# Sensing.net
KiCad netlist of a schematic drawn in Altium Designer
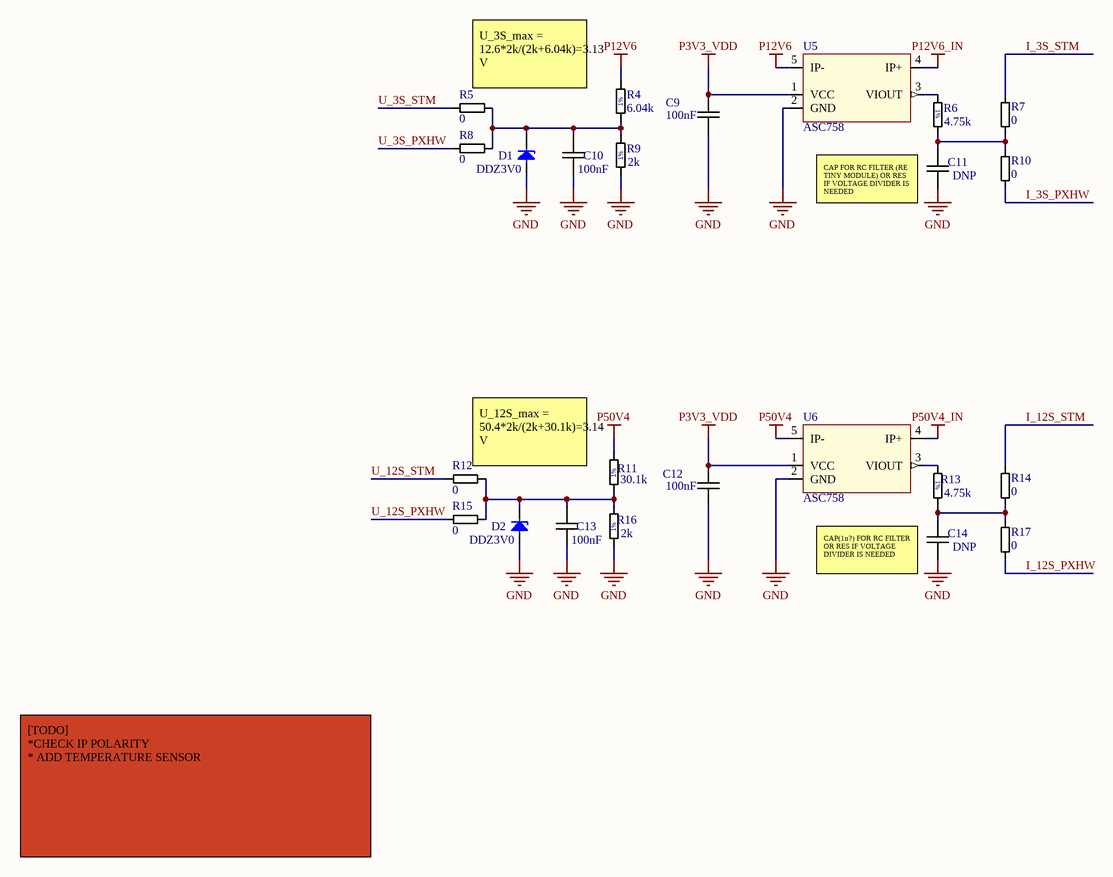
[diagram p0: Sensing.SchDoc]

(export (version "E")
  (design (tool "Eeschema 10.0.6"))
  (components
    (comp (ref "C9")
      (value "100nF")
      (footprint "CAPC0603X90N")
      (description "Non-polarised capacitor")
      (fields
        (field (name "MANUFACTURER") "GENERIC")
        (field (name "MANUFACTURER PART NUMBER") "CC0603_100NF_16V_10%_X7R")
        (field (name "AUTHOR") "KB")
      )
      (libsource (lib "Capacitors") (part "Capacitor - non polarized"))
    )
    (comp (ref "C10")
      (value "100nF")
      (footprint "CAPC0603X90N")
      (description "Non-polarised capacitor")
      (fields
        (field (name "MANUFACTURER") "GENERIC")
        (field (name "MANUFACTURER PART NUMBER") "CC0603_100NF_16V_10%_X7R")
        (field (name "AUTHOR") "KB")
      )
      (libsource (lib "Capacitors") (part "Capacitor - non polarized"))
    )
    (comp (ref "C11")
      (value "DNP")
      (footprint "CAPC0603X90N")
      (description "Non-polarised capacitor")
      (fields
        (field (name "MANUFACTURER") "GENERIC")
        (field (name "MANUFACTURER PART NUMBER") "UNDEFINED")
        (field (name "AUTHOR") "KB")
      )
      (libsource (lib "Capacitors") (part "Capacitor - non polarized"))
    )
    (comp (ref "C12")
      (value "100nF")
      (footprint "CAPC0603X90N")
      (description "Non-polarised capacitor")
      (fields
        (field (name "MANUFACTURER") "GENERIC")
        (field (name "MANUFACTURER PART NUMBER") "CC0603_100NF_16V_10%_X7R")
        (field (name "AUTHOR") "KB")
      )
      (libsource (lib "Capacitors") (part "Capacitor - non polarized"))
    )
    (comp (ref "C13")
      (value "100nF")
      (footprint "CAPC0603X90N")
      (description "Non-polarised capacitor")
      (fields
        (field (name "MANUFACTURER") "GENERIC")
        (field (name "MANUFACTURER PART NUMBER") "CC0603_100NF_16V_10%_X7R")
        (field (name "AUTHOR") "KB")
      )
      (libsource (lib "Capacitors") (part "Capacitor - non polarized"))
    )
    (comp (ref "C14")
      (value "DNP")
      (footprint "CAPC0603X90N")
      (description "Non-polarised capacitor")
      (fields
        (field (name "MANUFACTURER") "GENERIC")
        (field (name "MANUFACTURER PART NUMBER") "UNDEFINED")
        (field (name "AUTHOR") "KB")
      )
      (libsource (lib "Capacitors") (part "Capacitor - non polarized"))
    )
    (comp (ref "D1")
      (value "DDZ3V0")
      (footprint "SOD323F-ZENER")
      (description "Diode Zener, Uz 3.12V, 500mW")
      (fields (field (name "MANUFACTURER 1 PART NUMBER") "DDZ3V0BSF-7") (field (name "AUTHOR") "PC"))
      (libsource (lib "ICs And Semiconductors") (part "Diode Zener C1A2"))
    )
    (comp (ref "D2")
      (value "DDZ3V0")
      (footprint "SOD323F-ZENER")
      (description "Diode Zener, Uz 3.12V, 500mW")
      (fields (field (name "MANUFACTURER 1 PART NUMBER") "DDZ3V0BSF-7") (field (name "AUTHOR") "PC"))
      (libsource (lib "ICs And Semiconductors") (part "Diode Zener C1A2"))
    )
    (comp (ref "R4")
      (value "6.04k")
      (footprint "RESC0603X60N")
      (description "General Purpose Thick Film Chip Resistor")
      (fields
        (field (name "MANUFACTURER") "GENERIC")
        (field (name "MANUFACTURER PART NUMBER") "R0603_6K04_0.0625W 0.1W 0.125W 0.25W 0.5W 1W 0.75W 1W_100PPM")
        (field (name "AUTHOR") "KB")
      )
      (libsource (lib "Resistors") (part "Resistor - 1%"))
    )
    (comp (ref "R5")
      (value "0")
      (footprint "RESC0603X60N")
      (description "General Purpose Thick Film Chip Resistor")
      (fields
        (field (name "MANUFACTURER") "GENERIC")
        (field (name "MANUFACTURER PART NUMBER") "R0603_0R_JUMPER")
        (field (name "AUTHOR") "KB")
      )
      (libsource (lib "Resistors") (part "Resistor - Generic"))
    )
    (comp (ref "R6")
      (value "4.75k")
      (footprint "RESC0603X60N")
      (description "General Purpose Thick Film Chip Resistor")
      (fields
        (field (name "MANUFACTURER") "GENERIC")
        (field (name "MANUFACTURER PART NUMBER") "R0603_4K75_0.0625W 0.1W 0.125W 0.25W 0.5W 1W 0.75W 1W_100PPM")
        (field (name "AUTHOR") "KB")
      )
      (libsource (lib "Resistors") (part "Resistor - 1%"))
    )
    (comp (ref "R7")
      (value "0")
      (footprint "RESC0603X60N")
      (description "General Purpose Thick Film Chip Resistor")
      (fields
        (field (name "MANUFACTURER") "GENERIC")
        (field (name "MANUFACTURER PART NUMBER") "R0603_0R_JUMPER")
        (field (name "AUTHOR") "KB")
      )
      (libsource (lib "Resistors") (part "Resistor - Generic"))
    )
    (comp (ref "R8")
      (value "0")
      (footprint "RESC0603X60N")
      (description "General Purpose Thick Film Chip Resistor")
      (fields
        (field (name "MANUFACTURER") "GENERIC")
        (field (name "MANUFACTURER PART NUMBER") "R0603_0R_JUMPER")
        (field (name "AUTHOR") "KB")
      )
      (libsource (lib "Resistors") (part "Resistor - Generic"))
    )
    (comp (ref "R9")
      (value "2k")
      (footprint "RESC0603X60N")
      (description "General Purpose Thick Film Chip Resistor")
      (fields
        (field (name "MANUFACTURER") "GENERIC")
        (field (name "MANUFACTURER PART NUMBER") "R0603_2K00_0.0625W 0.1W 0.125W 0.25W 0.5W 1W 0.75W 1W_100PPM")
        (field (name "AUTHOR") "KB")
      )
      (libsource (lib "Resistors") (part "Resistor - 1%"))
    )
    (comp (ref "R10")
      (value "0")
      (footprint "RESC0603X60N")
      (description "General Purpose Thick Film Chip Resistor")
      (fields
        (field (name "MANUFACTURER") "GENERIC")
        (field (name "MANUFACTURER PART NUMBER") "R0603_0R_JUMPER")
        (field (name "AUTHOR") "KB")
      )
      (libsource (lib "Resistors") (part "Resistor - Generic"))
    )
    (comp (ref "R11")
      (value "30.1k")
      (footprint "RESC0603X60N")
      (description "General Purpose Thick Film Chip Resistor")
      (fields
        (field (name "MANUFACTURER") "GENERIC")
        (field (name "MANUFACTURER PART NUMBER") "R0603_30K1_0.0625W 0.1W 0.125W 0.25W 0.5W 1W 0.75W 1W_100PPM")
        (field (name "AUTHOR") "KB")
      )
      (libsource (lib "Resistors") (part "Resistor - 1%"))
    )
    (comp (ref "R12")
      (value "0")
      (footprint "RESC0603X60N")
      (description "General Purpose Thick Film Chip Resistor")
      (fields
        (field (name "MANUFACTURER") "GENERIC")
        (field (name "MANUFACTURER PART NUMBER") "R0603_0R_JUMPER")
        (field (name "AUTHOR") "KB")
      )
      (libsource (lib "Resistors") (part "Resistor - Generic"))
    )
    (comp (ref "R13")
      (value "4.75k")
      (footprint "RESC0603X60N")
      (description "General Purpose Thick Film Chip Resistor")
      (fields
        (field (name "MANUFACTURER") "GENERIC")
        (field (name "MANUFACTURER PART NUMBER") "R0603_4K75_0.0625W 0.1W 0.125W 0.25W 0.5W 1W 0.75W 1W_100PPM")
        (field (name "AUTHOR") "KB")
      )
      (libsource (lib "Resistors") (part "Resistor - 1%"))
    )
    (comp (ref "R14")
      (value "0")
      (footprint "RESC0603X60N")
      (description "General Purpose Thick Film Chip Resistor")
      (fields
        (field (name "MANUFACTURER") "GENERIC")
        (field (name "MANUFACTURER PART NUMBER") "R0603_0R_JUMPER")
        (field (name "AUTHOR") "KB")
      )
      (libsource (lib "Resistors") (part "Resistor - Generic"))
    )
    (comp (ref "R15")
      (value "0")
      (footprint "RESC0603X60N")
      (description "General Purpose Thick Film Chip Resistor")
      (fields
        (field (name "MANUFACTURER") "GENERIC")
        (field (name "MANUFACTURER PART NUMBER") "R0603_0R_JUMPER")
        (field (name "AUTHOR") "KB")
      )
      (libsource (lib "Resistors") (part "Resistor - Generic"))
    )
    (comp (ref "R16")
      (value "2k")
      (footprint "RESC0603X60N")
      (description "General Purpose Thick Film Chip Resistor")
      (fields
        (field (name "MANUFACTURER") "GENERIC")
        (field (name "MANUFACTURER PART NUMBER") "R0603_2K00_0.0625W 0.1W 0.125W 0.25W 0.5W 1W 0.75W 1W_100PPM")
        (field (name "AUTHOR") "KB")
      )
      (libsource (lib "Resistors") (part "Resistor - 1%"))
    )
    (comp (ref "R17")
      (value "0")
      (footprint "RESC0603X60N")
      (description "General Purpose Thick Film Chip Resistor")
      (fields
        (field (name "MANUFACTURER") "GENERIC")
        (field (name "MANUFACTURER PART NUMBER") "R0603_0R_JUMPER")
        (field (name "AUTHOR") "KB")
      )
      (libsource (lib "Resistors") (part "Resistor - Generic"))
    )
    (comp (ref "U5")
      (value "ASC758")
      (footprint "PFF")
      (description "Hall-Effect-Based\r\nLinear Current Sensor IC with 100 µ? Current Conductor")
      (fields (field (name "MANUFACTURER 1 PART NUMBER") "ACS758ECB-200B-PFF-T") (field (name "AUTHOR") "PC"))
      (libsource (lib "ICs And Semiconductors") (part "ASC758"))
    )
    (comp (ref "U6")
      (value "ASC758")
      (footprint "PFF")
      (description "Hall-Effect-Based\r\nLinear Current Sensor IC with 100 µ? Current Conductor")
      (fields (field (name "MANUFACTURER 1 PART NUMBER") "ACS758ECB-200B-PFF-T") (field (name "AUTHOR") "PC"))
      (libsource (lib "ICs And Semiconductors") (part "ASC758"))
    )
  )
  (nets
    (net (code "1") (name "/I_3S_PXHW") (class "Default")
      (node (ref "R10") (pin "1") (pinfunction "1_1") (pintype "passive"))
    )
    (net (code "2") (name "/I_3S_STM") (class "Default")
      (node (ref "R7") (pin "2") (pinfunction "2_2") (pintype "passive"))
    )
    (net (code "3") (name "/I_12S_PXHW") (class "Default")
      (node (ref "R17") (pin "1") (pinfunction "1_1") (pintype "passive"))
    )
    (net (code "4") (name "/I_12S_STM") (class "Default")
      (node (ref "R14") (pin "2") (pinfunction "2_2") (pintype "passive"))
    )
    (net (code "5") (name "/U_3S_PXHW") (class "Default")
      (node (ref "R8") (pin "2") (pinfunction "2_2") (pintype "passive"))
    )
    (net (code "6") (name "/U_3S_STM") (class "Default")
      (node (ref "R5") (pin "2") (pinfunction "2_2") (pintype "passive"))
    )
    (net (code "7") (name "/U_12S_PXHW") (class "Default")
      (node (ref "R15") (pin "2") (pinfunction "2_2") (pintype "passive"))
    )
    (net (code "8") (name "/U_12S_STM") (class "Default")
      (node (ref "R12") (pin "2") (pinfunction "2_2") (pintype "passive"))
    )
    (net (code "9") (name "GND") (class "Default")
      (node (ref "C10") (pin "1") (pinfunction "1_1") (pintype "passive"))
      (node (ref "C11") (pin "1") (pinfunction "1_1") (pintype "passive"))
      (node (ref "C12") (pin "1") (pinfunction "1_1") (pintype "passive"))
      (node (ref "C13") (pin "1") (pinfunction "1_1") (pintype "passive"))
      (node (ref "C14") (pin "1") (pinfunction "1_1") (pintype "passive"))
      (node (ref "C9") (pin "1") (pinfunction "1_1") (pintype "passive"))
      (node (ref "D1") (pin "2") (pinfunction "A_2") (pintype "passive"))
      (node (ref "D2") (pin "2") (pinfunction "A_2") (pintype "passive"))
      (node (ref "R16") (pin "1") (pinfunction "1_1") (pintype "passive"))
      (node (ref "R9") (pin "1") (pinfunction "1_1") (pintype "passive"))
      (node (ref "U5") (pin "2") (pinfunction "GND_2") (pintype "power_in"))
      (node (ref "U6") (pin "2") (pinfunction "GND_2") (pintype "power_in"))
    )
    (net (code "10") (name "Net-(C11-Pad2)") (class "Default")
      (node (ref "C11") (pin "2") (pinfunction "2_2") (pintype "passive"))
      (node (ref "R10") (pin "2") (pinfunction "2_2") (pintype "passive"))
      (node (ref "R6") (pin "2") (pinfunction "2_2") (pintype "passive"))
      (node (ref "R7") (pin "1") (pinfunction "1_1") (pintype "passive"))
    )
    (net (code "11") (name "Net-(C14-Pad2)") (class "Default")
      (node (ref "C14") (pin "2") (pinfunction "2_2") (pintype "passive"))
      (node (ref "R13") (pin "2") (pinfunction "2_2") (pintype "passive"))
      (node (ref "R14") (pin "1") (pinfunction "1_1") (pintype "passive"))
      (node (ref "R17") (pin "2") (pinfunction "2_2") (pintype "passive"))
    )
    (net (code "12") (name "Net-(D1-C)") (class "Default")
      (node (ref "C10") (pin "2") (pinfunction "2_2") (pintype "passive"))
      (node (ref "D1") (pin "1") (pinfunction "C_1") (pintype "passive"))
      (node (ref "R4") (pin "1") (pinfunction "1_1") (pintype "passive"))
      (node (ref "R5") (pin "1") (pinfunction "1_1") (pintype "passive"))
      (node (ref "R8") (pin "1") (pinfunction "1_1") (pintype "passive"))
      (node (ref "R9") (pin "2") (pinfunction "2_2") (pintype "passive"))
    )
    (net (code "13") (name "Net-(D2-C)") (class "Default")
      (node (ref "C13") (pin "2") (pinfunction "2_2") (pintype "passive"))
      (node (ref "D2") (pin "1") (pinfunction "C_1") (pintype "passive"))
      (node (ref "R11") (pin "1") (pinfunction "1_1") (pintype "passive"))
      (node (ref "R12") (pin "1") (pinfunction "1_1") (pintype "passive"))
      (node (ref "R15") (pin "1") (pinfunction "1_1") (pintype "passive"))
      (node (ref "R16") (pin "2") (pinfunction "2_2") (pintype "passive"))
    )
    (net (code "14") (name "Net-(U5-VIOUT)") (class "Default")
      (node (ref "R6") (pin "1") (pinfunction "1_1") (pintype "passive"))
      (node (ref "U5") (pin "3") (pinfunction "VIOUT_3") (pintype "output"))
    )
    (net (code "15") (name "Net-(U6-VIOUT)") (class "Default")
      (node (ref "R13") (pin "1") (pinfunction "1_1") (pintype "passive"))
      (node (ref "U6") (pin "3") (pinfunction "VIOUT_3") (pintype "output"))
    )
    (net (code "16") (name "P3V3_VDD") (class "Default")
      (node (ref "C12") (pin "2") (pinfunction "2_2") (pintype "passive"))
      (node (ref "C9") (pin "2") (pinfunction "2_2") (pintype "passive"))
      (node (ref "U5") (pin "1") (pinfunction "VCC_1") (pintype "power_in"))
      (node (ref "U6") (pin "1") (pinfunction "VCC_1") (pintype "power_in"))
    )
    (net (code "17") (name "P12V6") (class "Default")
      (node (ref "R4") (pin "2") (pinfunction "2_2") (pintype "passive"))
      (node (ref "U5") (pin "5") (pinfunction "IP-_5") (pintype "power_in"))
    )
    (net (code "18") (name "P12V6_IN") (class "Default")
      (node (ref "U5") (pin "4") (pinfunction "IP+_4") (pintype "power_in"))
    )
    (net (code "19") (name "P50V4") (class "Default")
      (node (ref "R11") (pin "2") (pinfunction "2_2") (pintype "passive"))
      (node (ref "U6") (pin "5") (pinfunction "IP-_5") (pintype "power_in"))
    )
    (net (code "20") (name "P50V4_IN") (class "Default")
      (node (ref "U6") (pin "4") (pinfunction "IP+_4") (pintype "power_in"))
    )
  )
)
